# 701_PCIe-USBports.net
KiCad netlist of a schematic drawn in Altium Designer
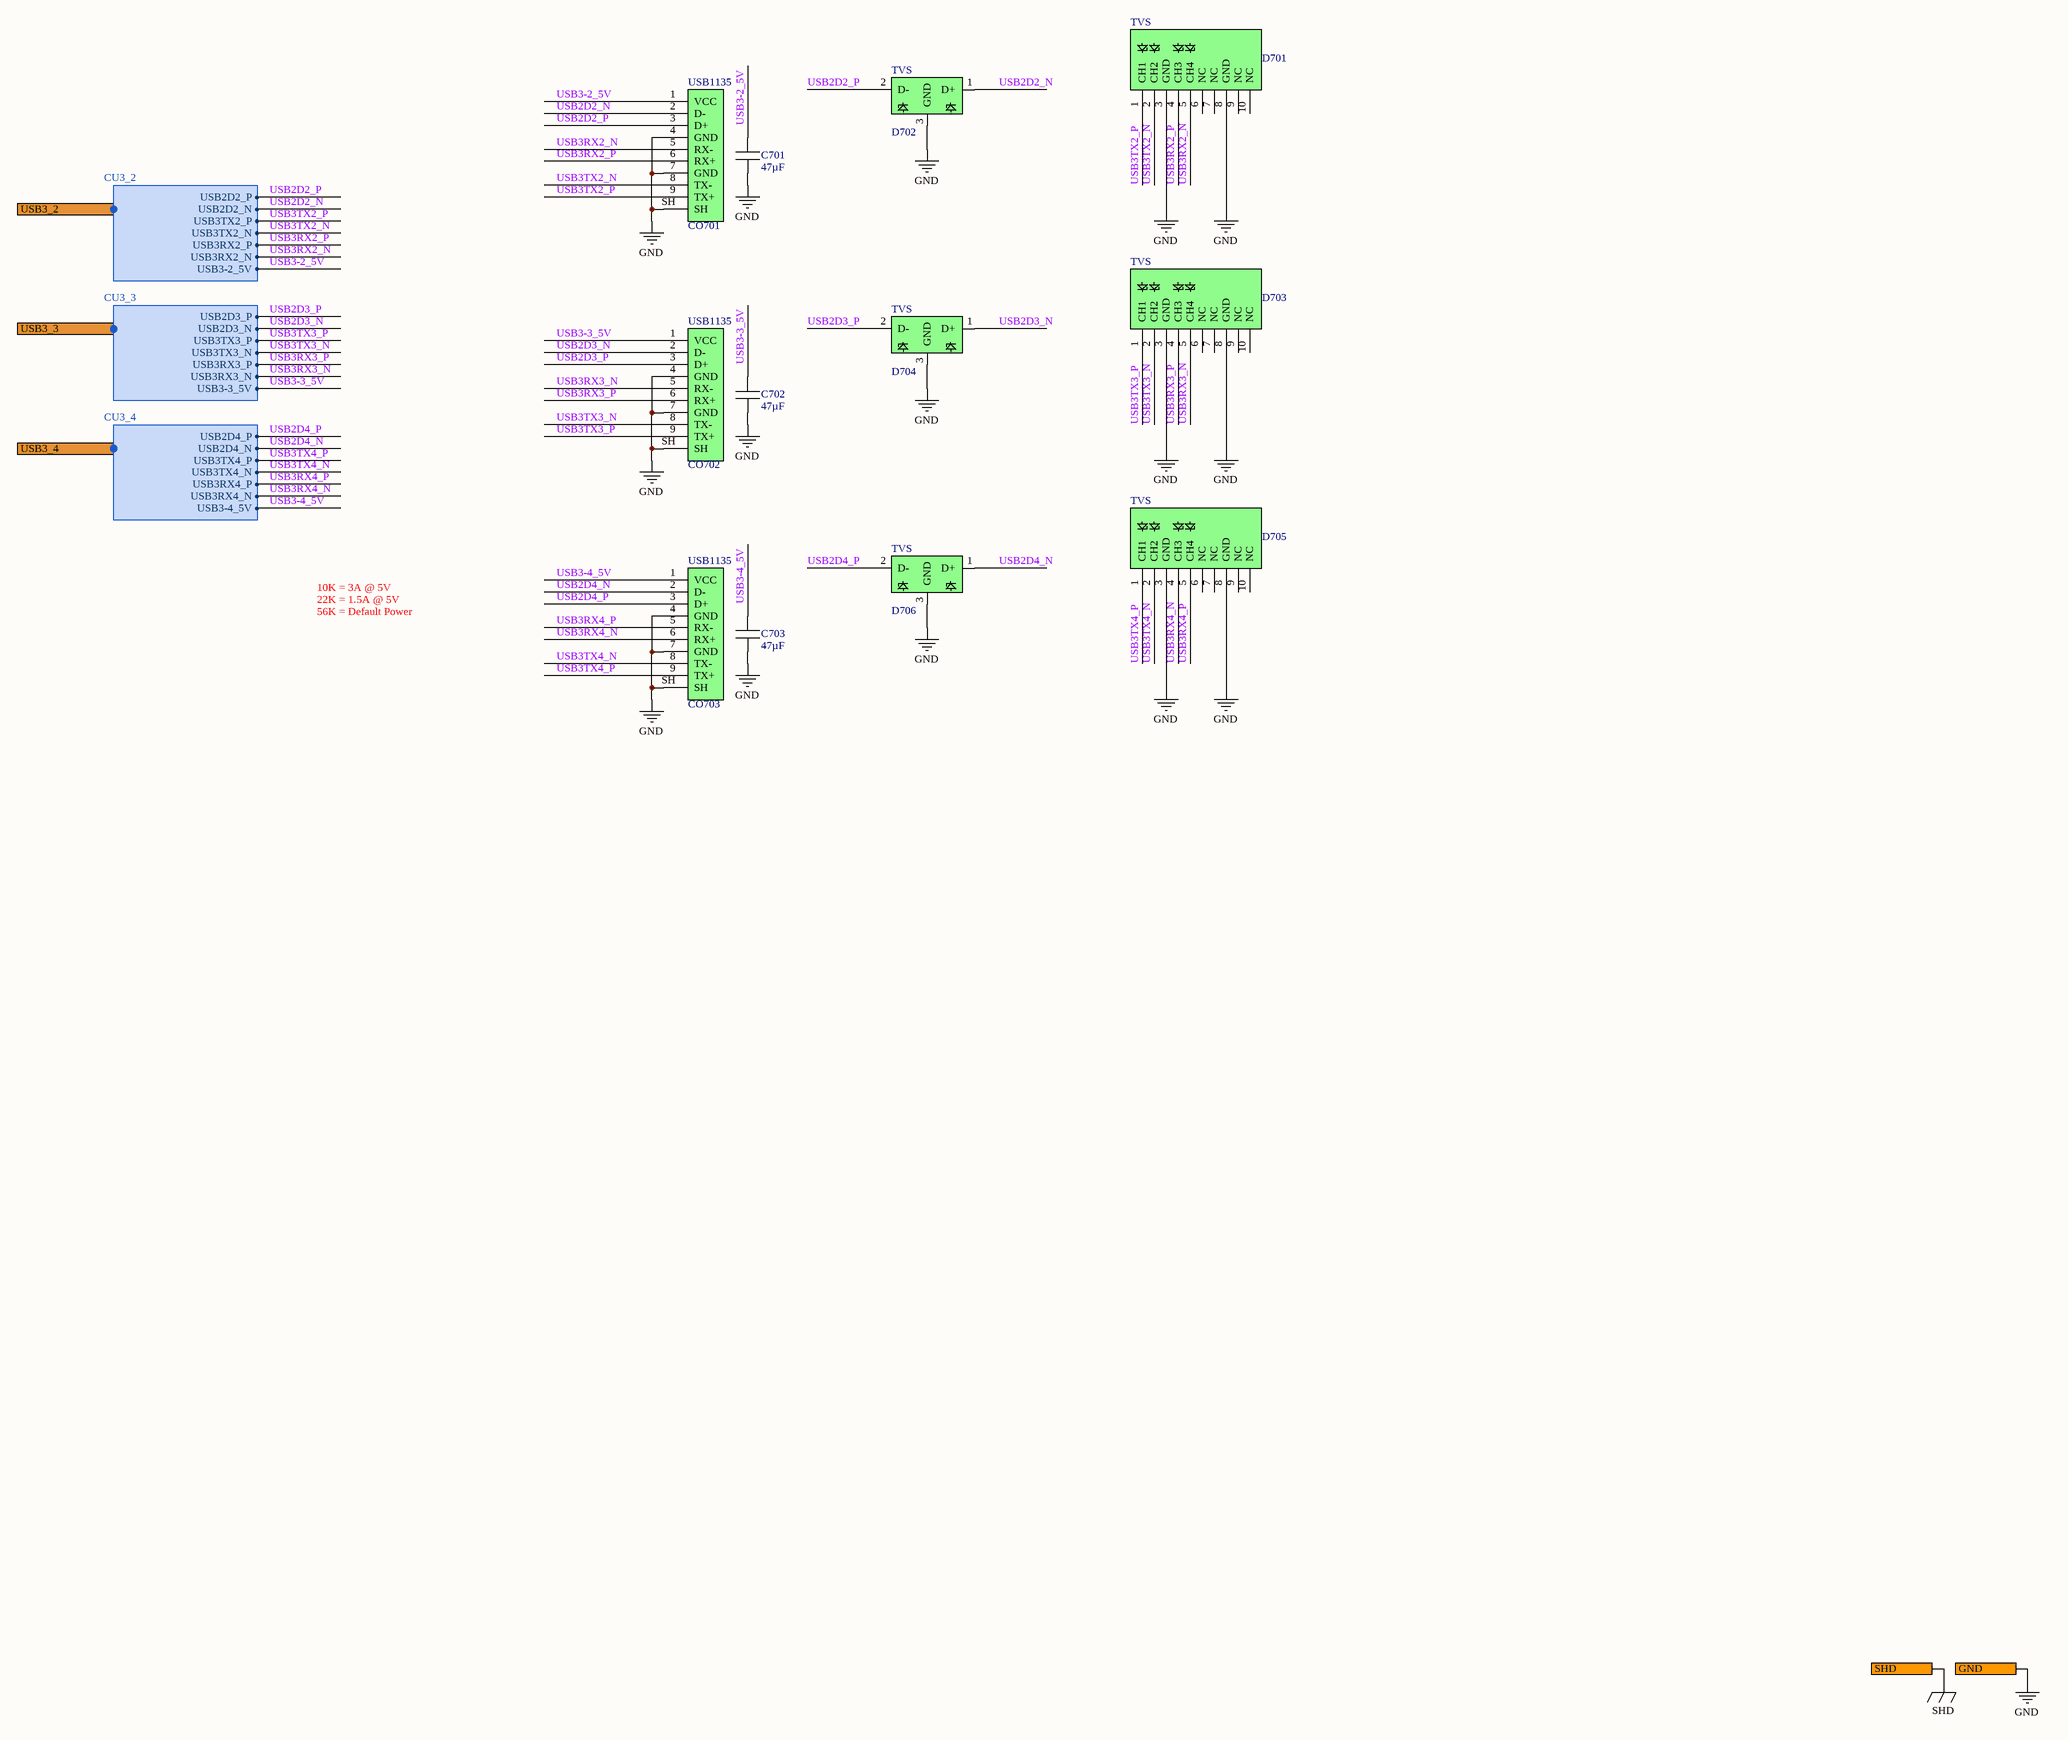
[diagram p0: 701_PCIe-USBports.SchDoc]

(export (version "E")
  (design (tool "Eeschema 10.0.6"))
  (components
    (comp (ref "C701")
      (value "47µF")
      (footprint "C1210")
      (description "47µF 16V 20% X5R")
      (fields
        (field (name "REFVAL") "47µF")
        (field (name "PART NUMBER") "CA0007")
        (field (name "MANFACTPART") "EMK325ABJ476MM8P")
      )
      (libsource (lib "GTS_Database") (part "C"))
    )
    (comp (ref "C702")
      (value "47µF")
      (footprint "C1210")
      (description "47µF 16V 20% X5R")
      (fields
        (field (name "REFVAL") "47µF")
        (field (name "PART NUMBER") "CA0007")
        (field (name "MANFACTPART") "EMK325ABJ476MM8P")
      )
      (libsource (lib "GTS_Database") (part "C"))
    )
    (comp (ref "C703")
      (value "47µF")
      (footprint "C1210")
      (description "47µF 16V 20% X5R")
      (fields
        (field (name "REFVAL") "47µF")
        (field (name "PART NUMBER") "CA0007")
        (field (name "MANFACTPART") "EMK325ABJ476MM8P")
      )
      (libsource (lib "GTS_Database") (part "C"))
    )
    (comp (ref "CO701")
      (value "USB1135")
      (footprint "USB1135-15-9-L-B")
      (description "USB3.0 Type A receptacle Horizontal")
      (fields
        (field (name "REFVAL") "USB1135")
        (field (name "PART NUMBER") "CO0041")
        (field (name "MANFACTPART") "USB1135-15-9-L-B")
      )
      (libsource (lib "GTS_Database") (part "USB3"))
    )
    (comp (ref "CO702")
      (value "USB1135")
      (footprint "USB1135-15-9-L-B")
      (description "USB3.0 Type A receptacle Horizontal")
      (fields
        (field (name "REFVAL") "USB1135")
        (field (name "PART NUMBER") "CO0041")
        (field (name "MANFACTPART") "USB1135-15-9-L-B")
      )
      (libsource (lib "GTS_Database") (part "USB3"))
    )
    (comp (ref "CO703")
      (value "USB1135")
      (footprint "USB1135-15-9-L-B")
      (description "USB3.0 Type A receptacle Horizontal")
      (fields
        (field (name "REFVAL") "USB1135")
        (field (name "PART NUMBER") "CO0041")
        (field (name "MANFACTPART") "USB1135-15-9-L-B")
      )
      (libsource (lib "GTS_Database") (part "USB3"))
    )
    (comp (ref "D701")
      (value "TVS")
      (footprint "SOT-1176-1")
      (description "USB 3 TVS Diode")
      (fields
        (field (name "REFVAL") "TVS")
        (field (name "PART NUMBER") "DI0007")
        (field (name "MANFACTPART") "PUSB3FA2Z")
      )
      (libsource (lib "GTS_Database") (part "USB3TVS"))
    )
    (comp (ref "D702")
      (value "TVS")
      (footprint "SOT-3")
      (description "USB 2 TVS Diode")
      (fields
        (field (name "REFVAL") "TVS")
        (field (name "PART NUMBER") "DI0002")
        (field (name "MANFACTPART") "TPD2EUSB30DRTR")
      )
      (libsource (lib "GTS_Database") (part "USB2TVS"))
    )
    (comp (ref "D703")
      (value "TVS")
      (footprint "SOT-1176-1")
      (description "USB 3 TVS Diode")
      (fields
        (field (name "REFVAL") "TVS")
        (field (name "PART NUMBER") "DI0007")
        (field (name "MANFACTPART") "PUSB3FA2Z")
      )
      (libsource (lib "GTS_Database") (part "USB3TVS"))
    )
    (comp (ref "D704")
      (value "TVS")
      (footprint "SOT-3")
      (description "USB 2 TVS Diode")
      (fields
        (field (name "REFVAL") "TVS")
        (field (name "PART NUMBER") "DI0002")
        (field (name "MANFACTPART") "TPD2EUSB30DRTR")
      )
      (libsource (lib "GTS_Database") (part "USB2TVS"))
    )
    (comp (ref "D705")
      (value "TVS")
      (footprint "SOT-1176-1")
      (description "USB 3 TVS Diode")
      (fields
        (field (name "REFVAL") "TVS")
        (field (name "PART NUMBER") "DI0007")
        (field (name "MANFACTPART") "PUSB3FA2Z")
      )
      (libsource (lib "GTS_Database") (part "USB3TVS"))
    )
    (comp (ref "D706")
      (value "TVS")
      (footprint "SOT-3")
      (description "USB 2 TVS Diode")
      (fields
        (field (name "REFVAL") "TVS")
        (field (name "PART NUMBER") "DI0002")
        (field (name "MANFACTPART") "TPD2EUSB30DRTR")
      )
      (libsource (lib "GTS_Database") (part "USB2TVS"))
    )
  )
  (nets
    (net (code "4") (name "/USB2D2_N") (class "Default")
      (node (ref "CO701") (pin "2") (pinfunction "D-_2") (pintype "passive"))
      (node (ref "D702") (pin "1") (pinfunction "D+_1") (pintype "passive"))
    )
    (net (code "5") (name "/USB2D2_P") (class "Default")
      (node (ref "CO701") (pin "3") (pinfunction "D+_3") (pintype "passive"))
      (node (ref "D702") (pin "2") (pinfunction "D-_2") (pintype "passive"))
    )
    (net (code "6") (name "/USB2D3_N") (class "Default")
      (node (ref "CO702") (pin "2") (pinfunction "D-_2") (pintype "passive"))
      (node (ref "D704") (pin "1") (pinfunction "D+_1") (pintype "passive"))
    )
    (net (code "7") (name "/USB2D3_P") (class "Default")
      (node (ref "CO702") (pin "3") (pinfunction "D+_3") (pintype "passive"))
      (node (ref "D704") (pin "2") (pinfunction "D-_2") (pintype "passive"))
    )
    (net (code "8") (name "/USB2D4_N") (class "Default")
      (node (ref "CO703") (pin "2") (pinfunction "D-_2") (pintype "passive"))
      (node (ref "D706") (pin "1") (pinfunction "D+_1") (pintype "passive"))
    )
    (net (code "9") (name "/USB2D4_P") (class "Default")
      (node (ref "CO703") (pin "3") (pinfunction "D+_3") (pintype "passive"))
      (node (ref "D706") (pin "2") (pinfunction "D-_2") (pintype "passive"))
    )
    (net (code "10") (name "/USB3-2_5V") (class "Default")
      (node (ref "C701") (pin "1") (pinfunction "1_1") (pintype "passive"))
      (node (ref "CO701") (pin "1") (pinfunction "VCC_1") (pintype "passive"))
    )
    (net (code "11") (name "/USB3-3_5V") (class "Default")
      (node (ref "C702") (pin "1") (pinfunction "1_1") (pintype "passive"))
      (node (ref "CO702") (pin "1") (pinfunction "VCC_1") (pintype "passive"))
    )
    (net (code "12") (name "/USB3-4_5V") (class "Default")
      (node (ref "C703") (pin "1") (pinfunction "1_1") (pintype "passive"))
      (node (ref "CO703") (pin "1") (pinfunction "VCC_1") (pintype "passive"))
    )
    (net (code "13") (name "/USB3RX2_N") (class "Default")
      (node (ref "CO701") (pin "5") (pinfunction "RX-_5") (pintype "passive"))
      (node (ref "D701") (pin "5") (pinfunction "CH4_5") (pintype "passive"))
    )
    (net (code "14") (name "/USB3RX2_P") (class "Default")
      (node (ref "CO701") (pin "6") (pinfunction "RX+_6") (pintype "passive"))
      (node (ref "D701") (pin "4") (pinfunction "CH3_4") (pintype "passive"))
    )
    (net (code "15") (name "/USB3RX3_N") (class "Default")
      (node (ref "CO702") (pin "5") (pinfunction "RX-_5") (pintype "passive"))
      (node (ref "D703") (pin "5") (pinfunction "CH4_5") (pintype "passive"))
    )
    (net (code "16") (name "/USB3RX3_P") (class "Default")
      (node (ref "CO702") (pin "6") (pinfunction "RX+_6") (pintype "passive"))
      (node (ref "D703") (pin "4") (pinfunction "CH3_4") (pintype "passive"))
    )
    (net (code "17") (name "/USB3RX4_N") (class "Default")
      (node (ref "CO703") (pin "6") (pinfunction "RX+_6") (pintype "passive"))
      (node (ref "D705") (pin "4") (pinfunction "CH3_4") (pintype "passive"))
    )
    (net (code "18") (name "/USB3RX4_P") (class "Default")
      (node (ref "CO703") (pin "5") (pinfunction "RX-_5") (pintype "passive"))
      (node (ref "D705") (pin "5") (pinfunction "CH4_5") (pintype "passive"))
    )
    (net (code "19") (name "/USB3TX2_N") (class "Default")
      (node (ref "CO701") (pin "8") (pinfunction "TX-_8") (pintype "passive"))
      (node (ref "D701") (pin "2") (pinfunction "CH2_2") (pintype "passive"))
    )
    (net (code "20") (name "/USB3TX2_P") (class "Default")
      (node (ref "CO701") (pin "9") (pinfunction "TX+_9") (pintype "passive"))
      (node (ref "D701") (pin "1") (pinfunction "CH1_1") (pintype "passive"))
    )
    (net (code "21") (name "/USB3TX3_N") (class "Default")
      (node (ref "CO702") (pin "8") (pinfunction "TX-_8") (pintype "passive"))
      (node (ref "D703") (pin "2") (pinfunction "CH2_2") (pintype "passive"))
    )
    (net (code "22") (name "/USB3TX3_P") (class "Default")
      (node (ref "CO702") (pin "9") (pinfunction "TX+_9") (pintype "passive"))
      (node (ref "D703") (pin "1") (pinfunction "CH1_1") (pintype "passive"))
    )
    (net (code "23") (name "/USB3TX4_N") (class "Default")
      (node (ref "CO703") (pin "8") (pinfunction "TX-_8") (pintype "passive"))
      (node (ref "D705") (pin "2") (pinfunction "CH2_2") (pintype "passive"))
    )
    (net (code "24") (name "/USB3TX4_P") (class "Default")
      (node (ref "CO703") (pin "9") (pinfunction "TX+_9") (pintype "passive"))
      (node (ref "D705") (pin "1") (pinfunction "CH1_1") (pintype "passive"))
    )
    (net (code "28") (name "GND") (class "Default")
      (node (ref "C701") (pin "2") (pinfunction "2_2") (pintype "passive"))
      (node (ref "C702") (pin "2") (pinfunction "2_2") (pintype "passive"))
      (node (ref "C703") (pin "2") (pinfunction "2_2") (pintype "passive"))
      (node (ref "CO701") (pin "4") (pinfunction "GND_4") (pintype "passive"))
      (node (ref "CO701") (pin "7") (pinfunction "GND_7") (pintype "passive"))
      (node (ref "CO701") (pin "SH") (pinfunction "SH_SH") (pintype "passive"))
      (node (ref "CO702") (pin "4") (pinfunction "GND_4") (pintype "passive"))
      (node (ref "CO702") (pin "7") (pinfunction "GND_7") (pintype "passive"))
      (node (ref "CO702") (pin "SH") (pinfunction "SH_SH") (pintype "passive"))
      (node (ref "CO703") (pin "4") (pinfunction "GND_4") (pintype "passive"))
      (node (ref "CO703") (pin "7") (pinfunction "GND_7") (pintype "passive"))
      (node (ref "CO703") (pin "SH") (pinfunction "SH_SH") (pintype "passive"))
      (node (ref "D701") (pin "3") (pinfunction "GND_3") (pintype "passive"))
      (node (ref "D701") (pin "8") (pinfunction "GND_8") (pintype "passive"))
      (node (ref "D702") (pin "3") (pinfunction "GND_3") (pintype "power_in"))
      (node (ref "D703") (pin "3") (pinfunction "GND_3") (pintype "passive"))
      (node (ref "D703") (pin "8") (pinfunction "GND_8") (pintype "passive"))
      (node (ref "D704") (pin "3") (pinfunction "GND_3") (pintype "power_in"))
      (node (ref "D705") (pin "3") (pinfunction "GND_3") (pintype "passive"))
      (node (ref "D705") (pin "8") (pinfunction "GND_8") (pintype "passive"))
      (node (ref "D706") (pin "3") (pinfunction "GND_3") (pintype "power_in"))
    )
    (net (code "30") (name "unconnected-(D701-NC-Pad6)") (class "Default")
      (node (ref "D701") (pin "6") (pinfunction "NC_6") (pintype "passive"))
    )
    (net (code "31") (name "unconnected-(D701-NC-Pad7)") (class "Default")
      (node (ref "D701") (pin "7") (pinfunction "NC_7") (pintype "passive"))
    )
    (net (code "32") (name "unconnected-(D701-NC-Pad9)") (class "Default")
      (node (ref "D701") (pin "9") (pinfunction "NC_9") (pintype "passive"))
    )
    (net (code "33") (name "unconnected-(D701-NC-Pad10)") (class "Default")
      (node (ref "D701") (pin "10") (pinfunction "NC_10") (pintype "passive"))
    )
    (net (code "34") (name "unconnected-(D703-NC-Pad6)") (class "Default")
      (node (ref "D703") (pin "6") (pinfunction "NC_6") (pintype "passive"))
    )
    (net (code "35") (name "unconnected-(D703-NC-Pad7)") (class "Default")
      (node (ref "D703") (pin "7") (pinfunction "NC_7") (pintype "passive"))
    )
    (net (code "36") (name "unconnected-(D703-NC-Pad9)") (class "Default")
      (node (ref "D703") (pin "9") (pinfunction "NC_9") (pintype "passive"))
    )
    (net (code "37") (name "unconnected-(D703-NC-Pad10)") (class "Default")
      (node (ref "D703") (pin "10") (pinfunction "NC_10") (pintype "passive"))
    )
    (net (code "38") (name "unconnected-(D705-NC-Pad6)") (class "Default")
      (node (ref "D705") (pin "6") (pinfunction "NC_6") (pintype "passive"))
    )
    (net (code "39") (name "unconnected-(D705-NC-Pad7)") (class "Default")
      (node (ref "D705") (pin "7") (pinfunction "NC_7") (pintype "passive"))
    )
    (net (code "40") (name "unconnected-(D705-NC-Pad9)") (class "Default")
      (node (ref "D705") (pin "9") (pinfunction "NC_9") (pintype "passive"))
    )
    (net (code "41") (name "unconnected-(D705-NC-Pad10)") (class "Default")
      (node (ref "D705") (pin "10") (pinfunction "NC_10") (pintype "passive"))
    )
  )
)
